# SAMC21N_Xplained_Pro_Peripherals.net
KiCad netlist of a schematic drawn in Altium Designer
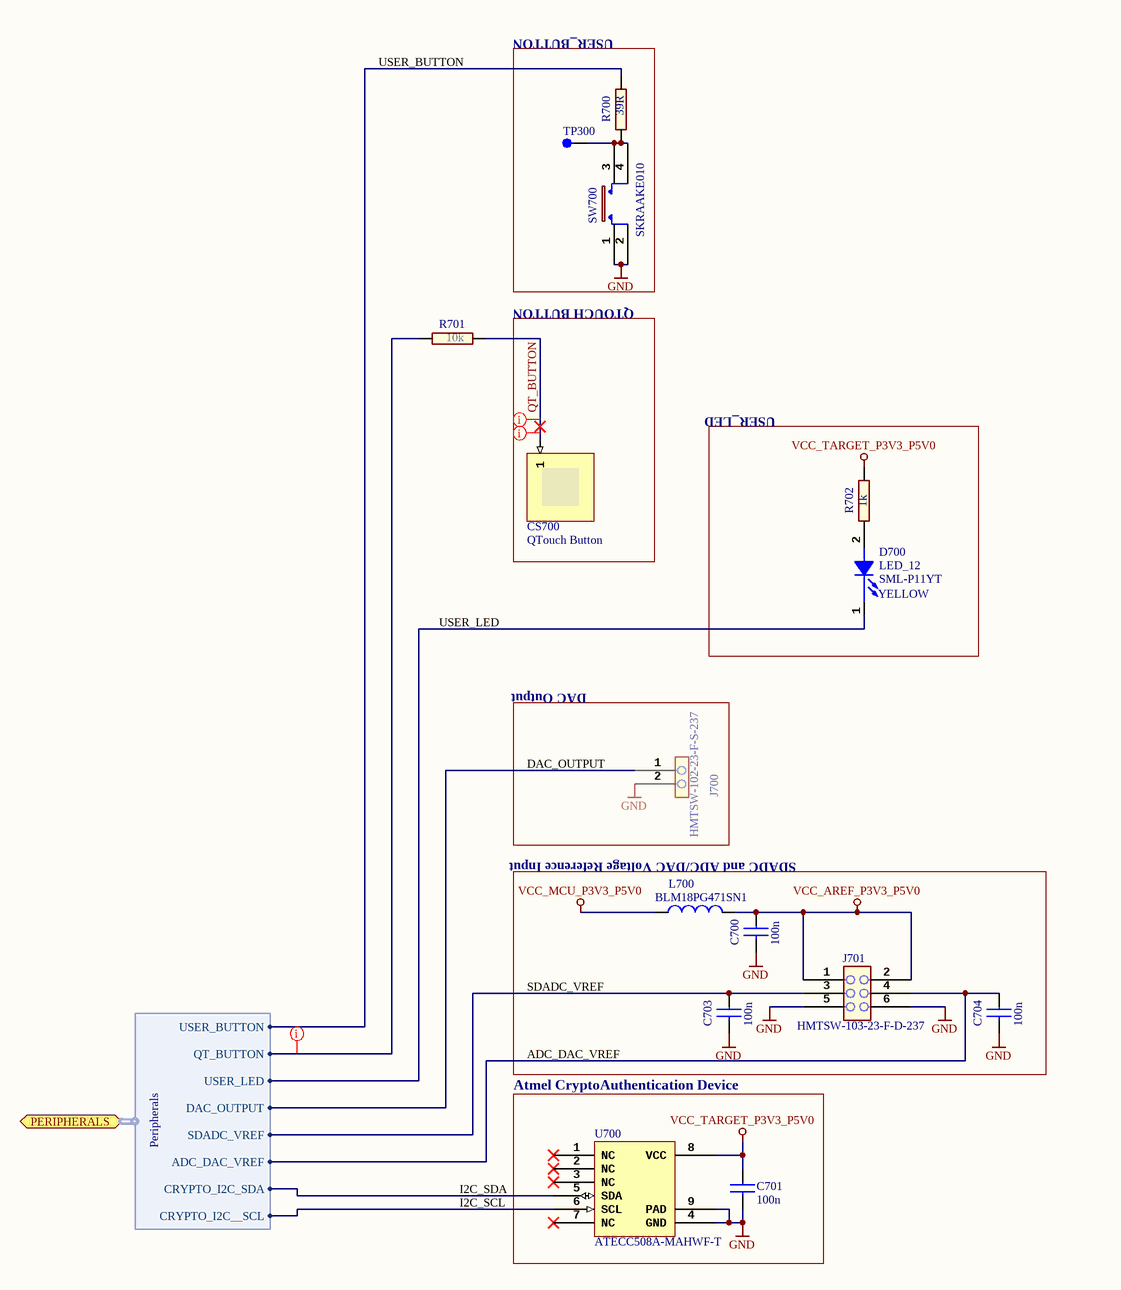
[diagram p0: SAMC21N_Xplained_Pro_Peripherals.SchDoc]

(export (version "E")
  (design (tool "Eeschema 10.0.6"))
  (components
    (comp (ref "C700")
      (value "100n")
      (footprint "AP1-00001")
      (description "Ceramic capacitor, SMD 0402, X7R, 16V, +/-10%")
      (fields
        (field (name "TOLERANCE") "16V, +/-10%")
        (field (name "MANUFACTURER") "Kemet")
        (field (name "VERIFIED BY") "Lars Helge Mo")
      )
      (libsource (lib "AltiumDbLib") (part "CAP-NONPOL"))
    )
    (comp (ref "C701")
      (value "100n")
      (footprint "AP1-00001")
      (description "Ceramic capacitor, SMD 0402, X7R, 16V, +/-10%")
      (fields
        (field (name "TOLERANCE") "16V, +/-10%")
        (field (name "MANUFACTURER") "Kemet")
        (field (name "VERIFIED BY") "Lars Helge Mo")
      )
      (libsource (lib "AltiumDbLib") (part "CAP-NONPOL"))
    )
    (comp (ref "C703")
      (value "100n")
      (footprint "AP1-00001")
      (description "Ceramic capacitor, SMD 0402, X7R, 16V, +/-10%")
      (fields
        (field (name "TOLERANCE") "16V, +/-10%")
        (field (name "MANUFACTURER") "Kemet")
        (field (name "VERIFIED BY") "Lars Helge Mo")
      )
      (libsource (lib "AltiumDbLib") (part "CAP-NONPOL"))
    )
    (comp (ref "C704")
      (value "100n")
      (footprint "AP1-00001")
      (description "Ceramic capacitor, SMD 0402, X7R, 16V, +/-10%")
      (fields
        (field (name "TOLERANCE") "16V, +/-10%")
        (field (name "MANUFACTURER") "Kemet")
        (field (name "VERIFIED BY") "Lars Helge Mo")
      )
      (libsource (lib "AltiumDbLib") (part "CAP-NONPOL"))
    )
    (comp (ref "CS700") (value "QTouch Button") (libsource (lib "Atmel QTouch") (part "QTouchButton")))
    (comp (ref "D700")
      (value "LED_12")
      (footprint "AP4-00160")
      (description "LED, SMD 0402, Yellow, Wave length=586nm, 7.6mcd @ (1mA, 1.9Vf)")
      (fields
        (field (name "ALTIUM_VALUE") "SML-P11YT")
        (field (name "MANUFACTURER") "ROHM")
        (field (name "MPN") "SML-P11YT-T86")
        (field (name "VERIFIED BY") "Sveinung Helgeland")
      )
      (libsource (lib "AltiumDbLib") (part "LED_12"))
    )
    (comp (ref "J700")
      (value "HMTSW-102-23-F-S-237")
      (footprint "AP8-00733")
      (description "1x2 pin header, 2.54mm pitch, Pin-in-Paste THM")
      (fields
        (field (name "MANUFACTURER") "SAMTEC")
        (field (name "Comment") "HEADER 1x2")
        (field (name "VERIFIED BY") "Lars Helge")
      )
      (libsource (lib "AltiumDbLib") (part "HEADER 1x2"))
    )
    (comp (ref "J701")
      (value "HMTSW-103-23-F-D-237")
      (footprint "AP8-00182")
      (description "2x3 pin header, 2.54mm pitch, Pin-in-Paste THM")
      (fields
        (field (name "MANUFACTURER") "SAMTEC")
        (field (name "Comment") "HEADER 2x3")
        (field (name "VERIFIED BY") "Lars Helge Mo")
      )
      (libsource (lib "AltiumDbLib") (part "HEADER 2x3"))
    )
    (comp (ref "L700")
      (value "BLM18PG471SN1")
      (footprint "AP3-00005")
      (description "SMD RF inductor 0603. Z=470Ohm (@100MHz), Max R(dc)=0.65Ohm, Max current=1A")
      (fields
        (field (name "TOLERANCE") "±25%")
        (field (name "MANUFACTURER") "Murata")
        (field (name "VERIFIED BY") "Lars Helge Mo")
      )
      (libsource (lib "AltiumDbLib") (part "INDUCTOR"))
    )
    (comp (ref "R700")
      (value "39R")
      (footprint "AP2-00000")
      (description "Thick film resistor, SMD 0402, 1/16W, 1%")
      (fields
        (field (name "TOLERANCE") "1 %")
        (field (name "Comment") "R2")
        (field (name "VERIFIED BY") "Lars Helge Mo")
      )
      (libsource (lib "") (part "R2_1"))
    )
    (comp (ref "R701")
      (value "10k")
      (footprint "AP2-00000")
      (description "Thick film resistor, SMD 0402, 1/16W, 1%")
      (fields
        (field (name "TOLERANCE") "1 %")
        (field (name "MANUFACTURER") "vishay")
        (field (name "VERIFIED BY") "Lars Helge Mo")
      )
      (libsource (lib "AltiumDbLib") (part "R2"))
    )
    (comp (ref "R702")
      (value "1k")
      (footprint "AP2-00000")
      (description "Thick film resistor, SMD 0402, 1/16W, 1%")
      (fields
        (field (name "TOLERANCE") "1 %")
        (field (name "MANUFACTURER") "ASJ")
        (field (name "VERIFIED BY") "Lars Helge Mo")
      )
      (libsource (lib "") (part "R2_2"))
    )
    (comp (ref "SW700")
      (value "SKRAAKE010")
      (footprint "AP8-00137")
      (description "6.2x6.2 mm SMD tact switch, same as A08-0091 but less force is needed")
      (fields
        (field (name "MANUFACTURER") "ALPS")
        (field (name "Comment") "Can be ordered in low volumes from Mouser")
        (field (name "VERIFIED BY") "Ketil Skjerve")
      )
      (libsource (lib "AltiumDbLib") (part "PUSHBUTTON1"))
    )
    (comp (ref "TP300")
      (value "TESTPOINT")
      (footprint "AP8-00010")
      (description "Single SMD testpad")
      (fields (field (name "VERIFIED BY") "Sveinung Helgeland"))
      (libsource (lib "AltiumDbLib") (part "TESTPOINT"))
    )
    (comp (ref "U700")
      (value "ATECC508A-MAHWF-T")
      (footprint "AP6-00409")
      (description "Secure authentication and product validation device, EEPROM, I2C, 2.0 - 5.5V, UDFN8")
      (fields (field (name "MANUFACTURER") "ATMEL") (field (name "Comment") "ATECC108_UDFN"))
      (libsource (lib "AltiumDbLib") (part "ATECC108_UDFN"))
    )
  )
  (nets
    (net (code "2") (name "/ADC_DAC_VREF") (class "Default")
      (node (ref "C704") (pin "1") (pinfunction "1_1") (pintype "passive"))
      (node (ref "J701") (pin "4") (pinfunction "4_4") (pintype "passive"))
    )
    (net (code "3") (name "/CRYPTO_I2C_SDA") (class "Default")
      (node (ref "U700") (pin "5") (pinfunction "SDA_5") (pintype "bidirectional"))
    )
    (net (code "4") (name "/CRYPTO_I2C__SCL") (class "Default")
      (node (ref "U700") (pin "6") (pinfunction "SCL_6") (pintype "input"))
    )
    (net (code "5") (name "/DAC_OUTPUT") (class "Default")
      (node (ref "J700") (pin "1") (pinfunction "1_1") (pintype "passive"))
    )
    (net (code "6") (name "/QT_BUTTON") (class "Default")
      (node (ref "CS700") (pin "1") (pinfunction "1_1") (pintype "input"))
      (node (ref "R701") (pin "2") (pinfunction "2_2") (pintype "passive"))
    )
    (net (code "7") (name "/SDADC_VREF") (class "Default")
      (node (ref "C703") (pin "1") (pinfunction "1_1") (pintype "passive"))
      (node (ref "J701") (pin "3") (pinfunction "3_3") (pintype "passive"))
    )
    (net (code "8") (name "/USER_BUTTON") (class "Default")
      (node (ref "R700") (pin "2") (pinfunction "2_2") (pintype "passive"))
    )
    (net (code "9") (name "/USER_LED") (class "Default")
      (node (ref "D700") (pin "1") (pinfunction "CATHODE_1") (pintype "passive"))
    )
    (net (code "11") (name "GND") (class "Default")
      (node (ref "C700") (pin "2") (pinfunction "2_2") (pintype "passive"))
      (node (ref "C701") (pin "2") (pinfunction "2_2") (pintype "passive"))
      (node (ref "C703") (pin "2") (pinfunction "2_2") (pintype "passive"))
      (node (ref "C704") (pin "2") (pinfunction "2_2") (pintype "passive"))
      (node (ref "J700") (pin "2") (pinfunction "2_2") (pintype "passive"))
      (node (ref "J701") (pin "5") (pinfunction "5_5") (pintype "passive"))
      (node (ref "J701") (pin "6") (pinfunction "6_6") (pintype "passive"))
      (node (ref "SW700") (pin "1") (pinfunction "1_1") (pintype "passive"))
      (node (ref "SW700") (pin "2") (pinfunction "2_2") (pintype "passive"))
      (node (ref "U700") (pin "4") (pinfunction "GND_4") (pintype "power_in"))
      (node (ref "U700") (pin "9") (pinfunction "PAD_9") (pintype "power_in"))
    )
    (net (code "12") (name "Net-(D700-ANODE)") (class "Default")
      (node (ref "D700") (pin "2") (pinfunction "ANODE_2") (pintype "passive"))
      (node (ref "R702") (pin "1") (pinfunction "1_1") (pintype "passive"))
    )
    (net (code "13") (name "Net-(R700-Pad1)") (class "Default")
      (node (ref "R700") (pin "1") (pinfunction "1_1") (pintype "passive"))
      (node (ref "SW700") (pin "3") (pinfunction "3_3") (pintype "passive"))
      (node (ref "SW700") (pin "4") (pinfunction "4_4") (pintype "passive"))
      (node (ref "TP300") (pin "1") (pinfunction "1_1") (pintype "passive"))
    )
    (net (code "14") (name "VCC_AREF_P3V3_P5V0") (class "Default")
      (node (ref "C700") (pin "1") (pinfunction "1_1") (pintype "passive"))
      (node (ref "J701") (pin "1") (pinfunction "1_1") (pintype "passive"))
      (node (ref "J701") (pin "2") (pinfunction "2_2") (pintype "passive"))
      (node (ref "L700") (pin "2") (pinfunction "2_2") (pintype "passive"))
    )
    (net (code "15") (name "VCC_MCU_P3V3_P5V0") (class "Default")
      (node (ref "L700") (pin "1") (pinfunction "1_1") (pintype "passive"))
    )
    (net (code "16") (name "VCC_TARGET_P3V3_P5V0") (class "Default")
      (node (ref "C701") (pin "1") (pinfunction "1_1") (pintype "passive"))
      (node (ref "R702") (pin "2") (pinfunction "2_2") (pintype "passive"))
      (node (ref "U700") (pin "8") (pinfunction "VCC_8") (pintype "power_in"))
    )
    (net (code "17") (name "unconnected-(R701-Pad1)") (class "Default")
      (node (ref "R701") (pin "1") (pinfunction "1_1") (pintype "passive"))
    )
    (net (code "18") (name "unconnected-(U700-NC-Pad1)") (class "Default")
      (node (ref "U700") (pin "1") (pinfunction "NC_1") (pintype "passive+no_connect"))
    )
    (net (code "19") (name "unconnected-(U700-NC-Pad2)") (class "Default")
      (node (ref "U700") (pin "2") (pinfunction "NC_2") (pintype "passive+no_connect"))
    )
    (net (code "20") (name "unconnected-(U700-NC-Pad3)") (class "Default")
      (node (ref "U700") (pin "3") (pinfunction "NC_3") (pintype "passive+no_connect"))
    )
    (net (code "21") (name "unconnected-(U700-NC-Pad7)") (class "Default")
      (node (ref "U700") (pin "7") (pinfunction "NC_7") (pintype "passive+no_connect"))
    )
  )
)
